# VXX2SCH.net
KiCad netlist of a schematic drawn in Altium Designer
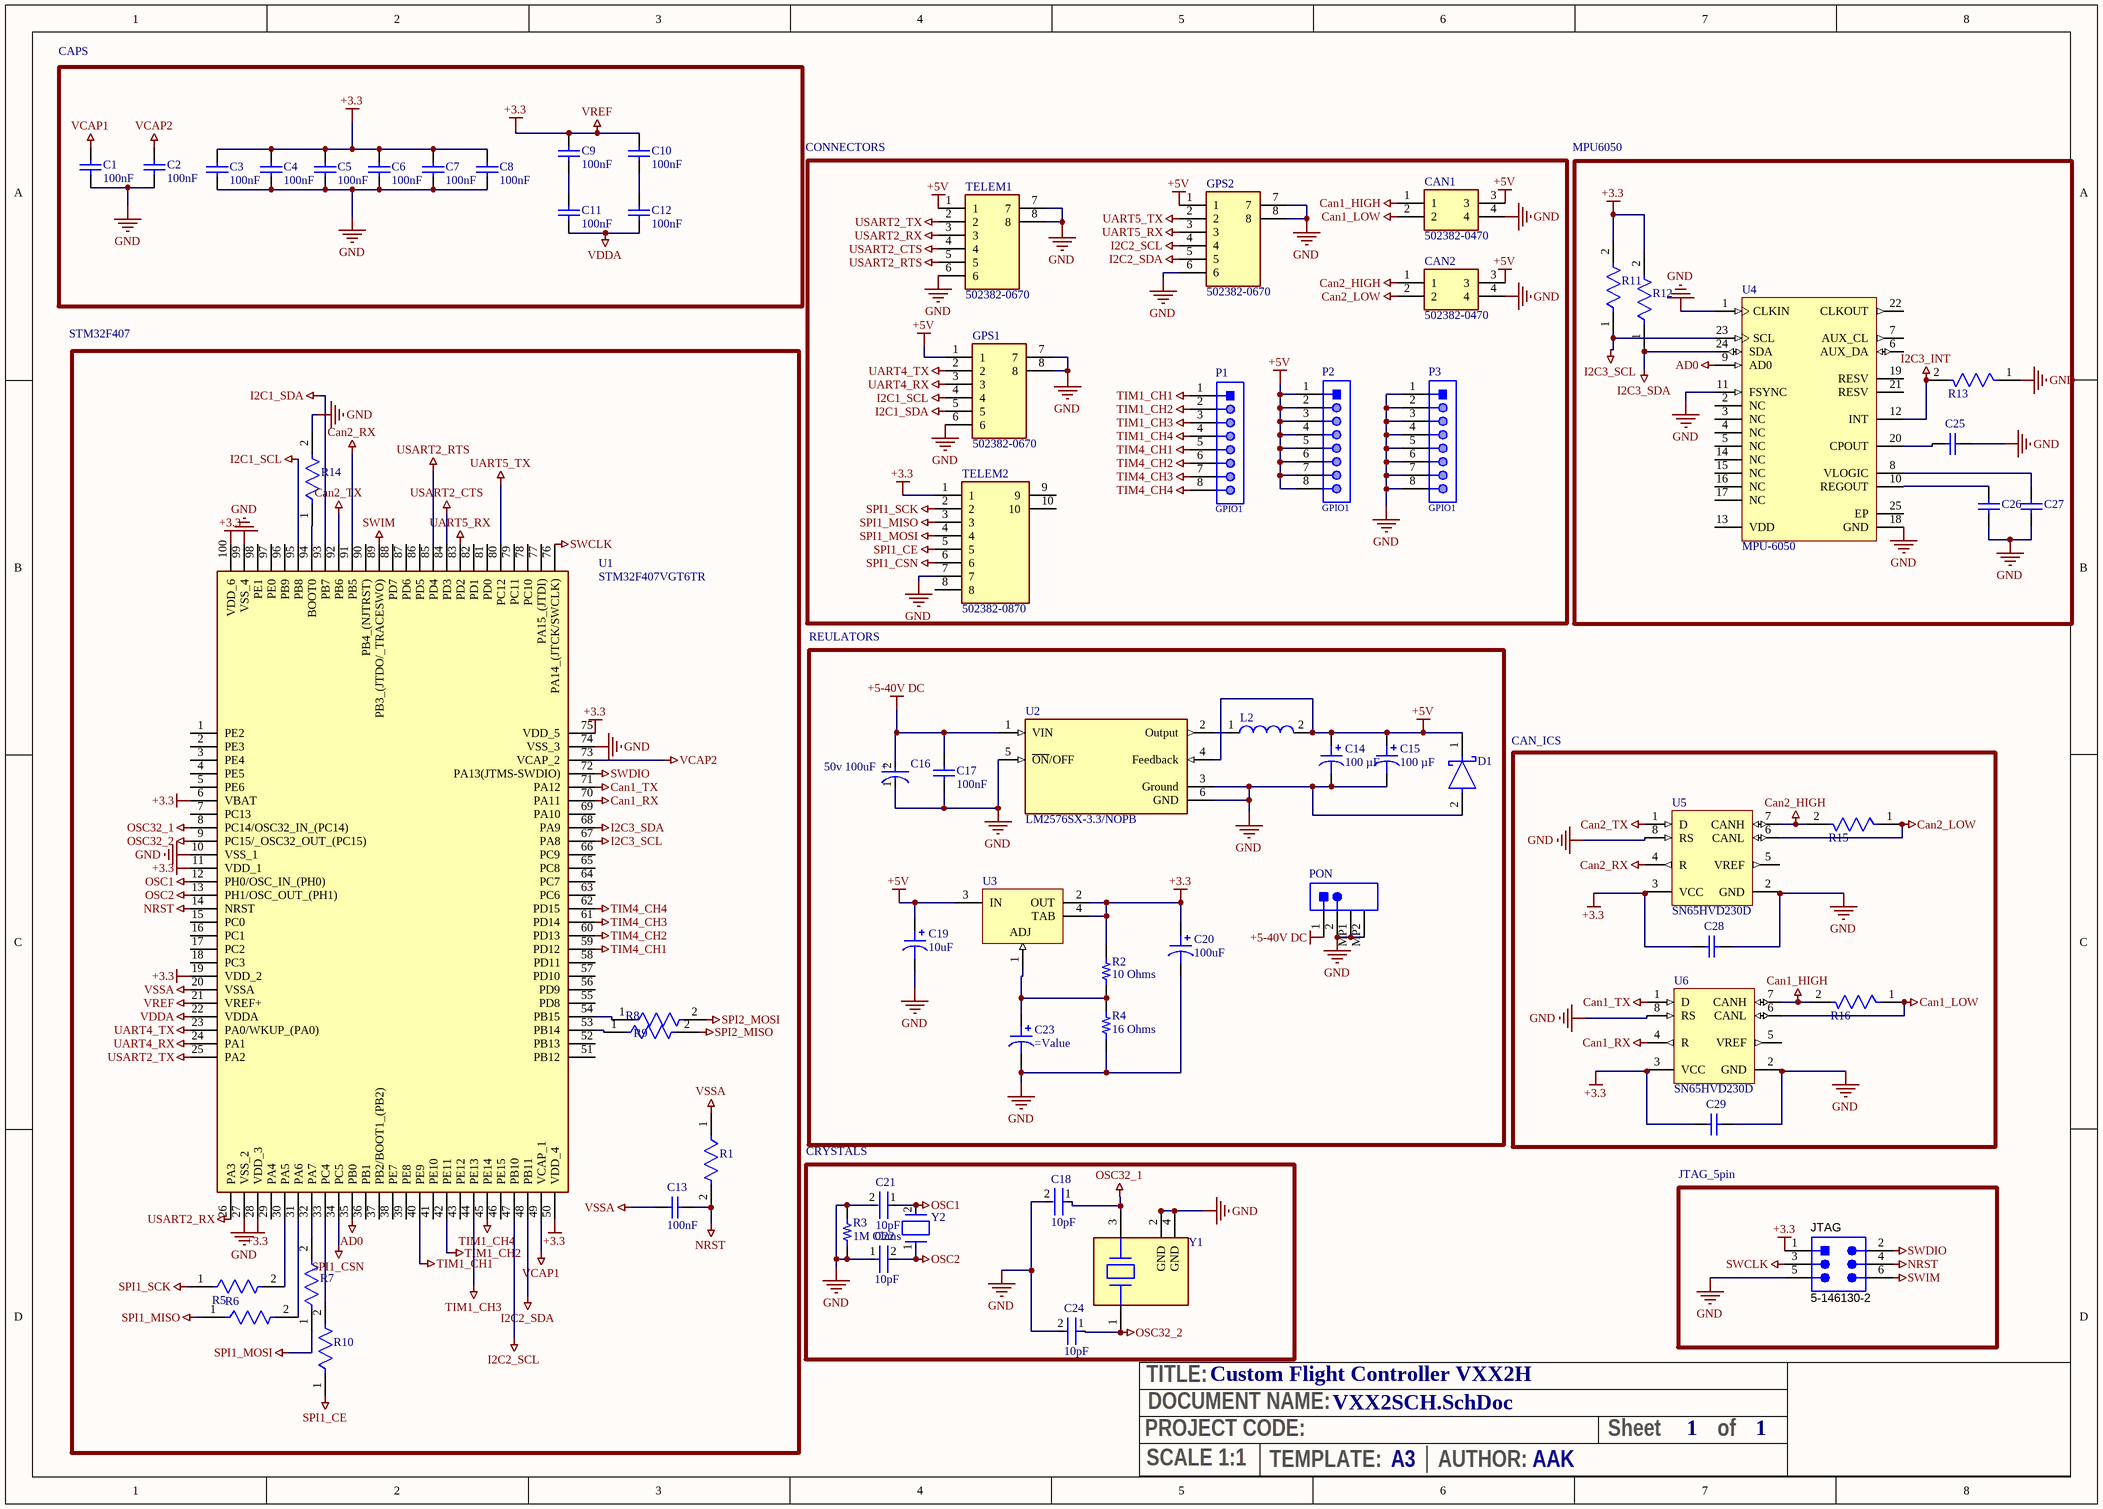
[diagram p0: VXX2SCH.SchDoc]

(export (version "E")
  (design (tool "Eeschema 10.0.6"))
  (components
    (comp (ref "C1")
      (value "100nF")
      (footprint "CAPC2013X135X45ML10T25")
      (description "Chip Capacitor, 0.1 uF, +/- 10%, 50 V, -55 to 125 degC, 0805 (2012 Metric), RoHS, Tape and Reel")
      (fields (field (name "VOLTAGE") "50V") (field (name "TOLERANCE") "10%"))
      (libsource (lib "Altium Content Vault") (part "CAP-NP-2"))
    )
    (comp (ref "C2")
      (value "100nF")
      (footprint "CAPC2013X135X45ML10T25")
      (description "Chip Capacitor, 0.1 uF, +/- 10%, 50 V, -55 to 125 degC, 0805 (2012 Metric), RoHS, Tape and Reel")
      (fields (field (name "VOLTAGE") "50V") (field (name "TOLERANCE") "10%"))
      (libsource (lib "Altium Content Vault") (part "CAP-NP-2"))
    )
    (comp (ref "C3")
      (value "100nF")
      (footprint "CAPC2013X135X45ML10T25")
      (description "Chip Capacitor, 0.1 uF, +/- 10%, 50 V, -55 to 125 degC, 0805 (2012 Metric), RoHS, Tape and Reel")
      (fields (field (name "VOLTAGE") "50V") (field (name "TOLERANCE") "10%"))
      (libsource (lib "Altium Content Vault") (part "CAP-NP-2"))
    )
    (comp (ref "C4")
      (value "100nF")
      (footprint "CAPC2013X135X45ML10T25")
      (description "Chip Capacitor, 0.1 uF, +/- 10%, 50 V, -55 to 125 degC, 0805 (2012 Metric), RoHS, Tape and Reel")
      (fields (field (name "VOLTAGE") "50V") (field (name "TOLERANCE") "10%"))
      (libsource (lib "Altium Content Vault") (part "CAP-NP-2"))
    )
    (comp (ref "C5")
      (value "100nF")
      (footprint "CAPC2013X135X45ML10T25")
      (description "Chip Capacitor, 0.1 uF, +/- 10%, 50 V, -55 to 125 degC, 0805 (2012 Metric), RoHS, Tape and Reel")
      (fields (field (name "VOLTAGE") "50V") (field (name "TOLERANCE") "10%"))
      (libsource (lib "Altium Content Vault") (part "CAP-NP-2"))
    )
    (comp (ref "C6")
      (value "100nF")
      (footprint "CAPC2013X135X45ML10T25")
      (description "Chip Capacitor, 0.1 uF, +/- 10%, 50 V, -55 to 125 degC, 0805 (2012 Metric), RoHS, Tape and Reel")
      (fields (field (name "VOLTAGE") "50V") (field (name "TOLERANCE") "10%"))
      (libsource (lib "Altium Content Vault") (part "CAP-NP-2"))
    )
    (comp (ref "C7")
      (value "100nF")
      (footprint "CAPC2013X135X45ML10T25")
      (description "Chip Capacitor, 0.1 uF, +/- 10%, 50 V, -55 to 125 degC, 0805 (2012 Metric), RoHS, Tape and Reel")
      (fields (field (name "VOLTAGE") "50V") (field (name "TOLERANCE") "10%"))
      (libsource (lib "Altium Content Vault") (part "CAP-NP-2"))
    )
    (comp (ref "C8")
      (value "100nF")
      (footprint "CAPC2013X135X45ML10T25")
      (description "Chip Capacitor, 0.1 uF, +/- 10%, 50 V, -55 to 125 degC, 0805 (2012 Metric), RoHS, Tape and Reel")
      (fields (field (name "VOLTAGE") "50V") (field (name "TOLERANCE") "10%"))
      (libsource (lib "Altium Content Vault") (part "CAP-NP-2"))
    )
    (comp (ref "C9")
      (value "100nF")
      (footprint "CAPC2013X135X45ML10T25")
      (description "Chip Capacitor, 0.1 uF, +/- 10%, 50 V, -55 to 125 degC, 0805 (2012 Metric), RoHS, Tape and Reel")
      (fields (field (name "VOLTAGE") "50V") (field (name "TOLERANCE") "10%"))
      (libsource (lib "Altium Content Vault") (part "CAP-NP-2"))
    )
    (comp (ref "C10")
      (value "100nF")
      (footprint "CAPC2013X135X45ML10T25")
      (description "Chip Capacitor, 0.1 uF, +/- 10%, 50 V, -55 to 125 degC, 0805 (2012 Metric), RoHS, Tape and Reel")
      (fields (field (name "VOLTAGE") "50V") (field (name "TOLERANCE") "10%"))
      (libsource (lib "Altium Content Vault") (part "CAP-NP-2"))
    )
    (comp (ref "C11")
      (value "100nF")
      (footprint "CAPC2013X135X45ML10T25")
      (description "Chip Capacitor, 0.1 uF, +/- 10%, 50 V, -55 to 125 degC, 0805 (2012 Metric), RoHS, Tape and Reel")
      (fields (field (name "VOLTAGE") "50V") (field (name "TOLERANCE") "10%"))
      (libsource (lib "Altium Content Vault") (part "CAP-NP-2"))
    )
    (comp (ref "C12")
      (value "100nF")
      (footprint "CAPC2013X135X45ML10T25")
      (description "Chip Capacitor, 0.1 uF, +/- 10%, 50 V, -55 to 125 degC, 0805 (2012 Metric), RoHS, Tape and Reel")
      (fields (field (name "VOLTAGE") "50V") (field (name "TOLERANCE") "10%"))
      (libsource (lib "Altium Content Vault") (part "CAP-NP-2"))
    )
    (comp (ref "C13")
      (value "100nF")
      (footprint "CAPC2013X135X45ML10T25")
      (description "Chip Capacitor, 0.1 uF, +/- 10%, 50 V, -55 to 125 degC, 0805 (2012 Metric), RoHS, Tape and Reel")
      (fields (field (name "VOLTAGE") "50V") (field (name "TOLERANCE") "10%"))
      (libsource (lib "Altium Content Vault") (part "CAP-NP-2"))
    )
    (comp (ref "C14")
      (value "100 µF")
      (footprint "CAP ALSMD 6.6MM H8.0MM")
      (description "CAP ALUM 100UF 20% 25V SMD")
      (fields (field (name "PART NUMBER") "UCD1E101MCL1GS") (field (name "MANUFACTURER") "Nichicon"))
      (libsource (lib "Celestial Altium Library - altium_library") (part "Polarised Capacitor"))
    )
    (comp (ref "C15")
      (value "100 µF")
      (footprint "CAP ALSMD 6.6MM H8.0MM")
      (description "CAP ALUM 100UF 20% 25V SMD")
      (fields (field (name "PART NUMBER") "UCD1E101MCL1GS") (field (name "MANUFACTURER") "Nichicon"))
      (libsource (lib "Celestial Altium Library - altium_library") (part "Polarised Capacitor"))
    )
    (comp (ref "C16")
      (value "50v 100uF")
      (footprint "FP-SC-MFG")
      (description "CAP ALUM 10UF 20% 35V SMD")
      (fields (field (name "TOLERANCE") "20%") (field (name "VOLTAGE") "35V"))
      (libsource (lib "Altium Content Vault") (part "203bc49f2ac43e59fd269a8c329ed05"))
    )
    (comp (ref "C17")
      (value "100nF")
      (footprint "CAPC2013X135X45ML10T25")
      (description "Chip Capacitor, 0.1 uF, +/- 10%, 50 V, -55 to 125 degC, 0805 (2012 Metric), RoHS, Tape and Reel")
      (fields (field (name "VOLTAGE") "50V") (field (name "TOLERANCE") "10%"))
      (libsource (lib "Altium Content Vault") (part "CAP-NP-2"))
    )
    (comp (ref "C18")
      (value "10pF")
      (footprint "FP-C0805C-DN-MFG")
      (description "Capacitor; Ceramic; Cap 10 pF; Tol 5%; Vol-Rtg 50 VDC; SMT; 0805; COG (NPO); Tape&Reel")
      (fields
        (field (name "OCTOPART") "https://octopart.com/c0805c100j5gactu-kemet-104357")
        (field (name "MANUFACTURER PART NUMBER") "C0805C100J5GACTU")
      )
      (libsource (lib "Altium Content Vault") (part "b4654b650e69147ec39a6b967a45e02"))
    )
    (comp (ref "C19")
      (value "10uF")
      (footprint "CAP ALSMD 4.3MM H5.4MM")
      (description "CAP ALUM 10UF 20% 16V SMD")
      (fields (field (name "PART NUMBER") "UWX1C100MCL1GB"))
      (libsource (lib "Celestial Altium Library - altium_library") (part "Polarised Capacitor"))
    )
    (comp (ref "C20")
      (value "100uF")
      (footprint "CAP ALSMD 4.3MM H5.4MM")
      (description "CAP ALUM 10UF 20% 16V SMD")
      (fields (field (name "PART NUMBER") "UWX1C100MCL1GB"))
      (libsource (lib "Celestial Altium Library - altium_library") (part "Polarised Capacitor"))
    )
    (comp (ref "C21")
      (value "10pF")
      (footprint "FP-C0805C-DN-MFG")
      (description "Capacitor; Ceramic; Cap 10 pF; Tol 5%; Vol-Rtg 50 VDC; SMT; 0805; COG (NPO); Tape&Reel")
      (fields
        (field (name "OCTOPART") "https://octopart.com/c0805c100j5gactu-kemet-104357")
        (field (name "MANUFACTURER PART NUMBER") "C0805C100J5GACTU")
      )
      (libsource (lib "Altium Content Vault") (part "b4654b650e69147ec39a6b967a45e02"))
    )
    (comp (ref "C22")
      (value "10pF")
      (footprint "FP-C0805C-DN-MFG")
      (description "Capacitor; Ceramic; Cap 10 pF; Tol 5%; Vol-Rtg 50 VDC; SMT; 0805; COG (NPO); Tape&Reel")
      (fields
        (field (name "OCTOPART") "https://octopart.com/c0805c100j5gactu-kemet-104357")
        (field (name "MANUFACTURER PART NUMBER") "C0805C100J5GACTU")
      )
      (libsource (lib "Altium Content Vault") (part "b4654b650e69147ec39a6b967a45e02"))
    )
    (comp (ref "C23")
      (value "~")
      (footprint "CAP ALSMD 4.3MM H5.4MM")
      (description "CAP ALUM 10UF 20% 16V SMD")
      (fields (field (name "PART NUMBER") "UWX1C100MCL1GB"))
      (libsource (lib "Celestial Altium Library - altium_library") (part "Polarised Capacitor"))
    )
    (comp (ref "C24")
      (value "10pF")
      (footprint "FP-C0805C-DN-MFG")
      (description "Capacitor; Ceramic; Cap 10 pF; Tol 5%; Vol-Rtg 50 VDC; SMT; 0805; COG (NPO); Tape&Reel")
      (fields
        (field (name "OCTOPART") "https://octopart.com/c0805c100j5gactu-kemet-104357")
        (field (name "MANUFACTURER PART NUMBER") "C0805C100J5GACTU")
      )
      (libsource (lib "Altium Content Vault") (part "b4654b650e69147ec39a6b967a45e02"))
    )
    (comp (ref "C25")
      (value "GRM188R71H222KA01D")
      (footprint "CAPC1608X90X35NL10T15")
      (description "Chip Capacitor, 2.2 nF, +/- 10%, 50 V, -55 to 125 degC, 0603 (1608 Metric), RoHS, Tape and Reel")
      (fields (field (name "MANUFACTURER") "Murata"))
      (libsource (lib "") (part "CAP-NP-2_1"))
    )
    (comp (ref "C26")
      (value "GRM188R71H222KA01D")
      (footprint "CAPC1608X90X35NL10T15")
      (description "Chip Capacitor, 2.2 nF, +/- 10%, 50 V, -55 to 125 degC, 0603 (1608 Metric), RoHS, Tape and Reel")
      (fields (field (name "MANUFACTURER") "Murata"))
      (libsource (lib "") (part "CAP-NP-2_1"))
    )
    (comp (ref "C27")
      (value "GRM188R71H222KA01D")
      (footprint "CAPC1608X90X35NL10T15")
      (description "Chip Capacitor, 2.2 nF, +/- 10%, 50 V, -55 to 125 degC, 0603 (1608 Metric), RoHS, Tape and Reel")
      (fields (field (name "MANUFACTURER") "Murata"))
      (libsource (lib "") (part "CAP-NP-2_1"))
    )
    (comp (ref "C28")
      (value "GRM188R71H222KA01D")
      (footprint "CAPC1608X90X35NL10T15")
      (description "Chip Capacitor, 2.2 nF, +/- 10%, 50 V, -55 to 125 degC, 0603 (1608 Metric), RoHS, Tape and Reel")
      (fields (field (name "MANUFACTURER") "Murata"))
      (libsource (lib "") (part "CAP-NP-2_1"))
    )
    (comp (ref "C29")
      (value "GRM188R71H222KA01D")
      (footprint "CAPC1608X90X35NL10T15")
      (description "Chip Capacitor, 2.2 nF, +/- 10%, 50 V, -55 to 125 degC, 0603 (1608 Metric), RoHS, Tape and Reel")
      (fields (field (name "MANUFACTURER") "Murata"))
      (libsource (lib "") (part "CAP-NP-2_1"))
    )
    (comp (ref "CAN1")
      (value "502382-0470")
      (footprint "SamacSys:502382-0470")
      (description "Connector")
      (fields (field (name "MOUSER PART NUMBER") "538-502382-0470"))
      (libsource (lib "*") (part "502382-0470"))
    )
    (comp (ref "CAN2")
      (value "502382-0470")
      (footprint "SamacSys:502382-0470")
      (description "Connector")
      (fields (field (name "MOUSER PART NUMBER") "538-502382-0470"))
      (libsource (lib "*") (part "502382-0470"))
    )
    (comp (ref "D1")
      (value "MBR0560-TP")
      (footprint "FP-SOD-123-IPC_C")
      (description "DIODE SCHOTTKY 60V 500MA SOD123")
      (libsource (lib "Altium Content Vault") (part "1d6ec82d83fb6aee721767c19dac4b9"))
    )
    (comp (ref "GPS1")
      (value "502382-0670")
      (footprint "SamacSys:5023820671")
      (description "Connector")
      (fields (field (name "MOUSER PART NUMBER") "538-502382-0670"))
      (libsource (lib "*") (part "502382-0670"))
    )
    (comp (ref "GPS2")
      (value "502382-0670")
      (footprint "SamacSys:5023820671")
      (description "Connector")
      (fields (field (name "MOUSER PART NUMBER") "538-502382-0670"))
      (libsource (lib "*") (part "502382-0670"))
    )
    (comp (ref "JTAG")
      (value "5-146130-2")
      (footprint "TECO-5-146130-2_V")
      (description "Male Header, Pitch 2.54 mm, 2 x 3 Position, Height 8.13 mm, -65 to 125 degC, RoHS, Tube")
      (libsource (lib "Altium Content Vault") (part "CN-2P-M-R6"))
    )
    (comp (ref "L2")
      (value "7447785147")
      (footprint "WE-PD-XS-PB")
      (description "SMD-Shielded Power Inductor WE-PD, L = 47.0 µH")
      (libsource (lib "Altium Content Vault") (part "PAS-IND-INDUCTOR-2"))
    )
    (comp (ref "P1")
      (value "GPIO1")
      (footprint "61300811121")
      (description "THT Vertical Pin Header WR-PHD, Pitch 2.54 mm, Single Row, 8 pins")
      (fields
        (field (name "MANUFACTURER") "Wurth Elektronik")
        (field (name "PART NUMBER") "61300811121")
        (field (name "PUBLISHER") "WurthElektronik")
      )
      (libsource (lib "Altium Content Vault") (part "WE-CN-1P-M-R8"))
    )
    (comp (ref "P2")
      (value "GPIO1")
      (footprint "61300811121")
      (description "THT Vertical Pin Header WR-PHD, Pitch 2.54 mm, Single Row, 8 pins")
      (fields
        (field (name "MANUFACTURER") "Wurth Elektronik")
        (field (name "PART NUMBER") "61300811121")
        (field (name "PUBLISHER") "WurthElektronik")
      )
      (libsource (lib "Altium Content Vault") (part "WE-CN-1P-M-R8"))
    )
    (comp (ref "P3")
      (value "GPIO1")
      (footprint "61300811121")
      (description "THT Vertical Pin Header WR-PHD, Pitch 2.54 mm, Single Row, 8 pins")
      (fields
        (field (name "MANUFACTURER") "Wurth Elektronik")
        (field (name "PART NUMBER") "61300811121")
        (field (name "PUBLISHER") "WurthElektronik")
      )
      (libsource (lib "Altium Content Vault") (part "WE-CN-1P-M-R8"))
    )
    (comp (ref "PON")
      (value "53398-0271")
      (footprint "MOLX-53398-0271_V")
      (description "Male Header, Pitch 1.25 mm, 1 x 2 Position, Height 4.7 mm, -40 to 85 degC, RoHS, Tape and Reel")
      (fields (field (name "MANUFACTURER") "Molex"))
      (libsource (lib "Altium Content Vault") (part "CN-1P-2M-R2"))
    )
    (comp (ref "R1")
      (value "RC0603FR-0710KL")
      (footprint "FP-RC0603-0_55-IPC_C")
      (description "RES 10K OHM 1% 1/10W 0603")
      (fields (field (name "TOLERANCE") "1%"))
      (libsource (lib "Altium Content Vault") (part "1029c3af85768c4190bb7ad29bc67b5"))
    )
    (comp (ref "R2")
      (value "10 Ohms")
      (footprint "RES 0603_1608")
      (description "RES 10K OHM 0.1% 1/16W 0603")
      (fields
        (field (name "PART NUMBER") "RNCS0603BKE10K0")
        (field (name "MANUFACTURER") "Stackpole Electronics Inc")
      )
      (libsource (lib "Celestial Altium Library - altium_library") (part "Resistor"))
    )
    (comp (ref "R3")
      (value "1M Ohms")
      (footprint "RES 0603_1608")
      (description "RES 10K OHM 0.1% 1/16W 0603")
      (fields
        (field (name "PART NUMBER") "RNCS0603BKE10K0")
        (field (name "MANUFACTURER") "Stackpole Electronics Inc")
      )
      (libsource (lib "Celestial Altium Library - altium_library") (part "Resistor"))
    )
    (comp (ref "R4")
      (value "16 Ohms")
      (footprint "RES 0603_1608")
      (description "RES 10K OHM 0.1% 1/16W 0603")
      (fields
        (field (name "PART NUMBER") "RNCS0603BKE10K0")
        (field (name "MANUFACTURER") "Stackpole Electronics Inc")
      )
      (libsource (lib "Celestial Altium Library - altium_library") (part "Resistor"))
    )
    (comp (ref "R5")
      (value "RC0603FR-07100L")
      (footprint "FP-RC0603-0_55-IPC_C")
      (description "RES 100 OHM 1% 1/10W 0603")
      (fields (field (name "TOLERANCE") "1%"))
      (libsource (lib "Altium Content Vault") (part "1029c3af85768c4190bb7ad29bc67b5"))
    )
    (comp (ref "R6")
      (value "RC0603FR-07100L")
      (footprint "FP-RC0603-0_55-IPC_C")
      (description "RES 100 OHM 1% 1/10W 0603")
      (fields (field (name "TOLERANCE") "1%"))
      (libsource (lib "Altium Content Vault") (part "1029c3af85768c4190bb7ad29bc67b5"))
    )
    (comp (ref "R7")
      (value "RC0603FR-07100L")
      (footprint "FP-RC0603-0_55-IPC_C")
      (description "RES 100 OHM 1% 1/10W 0603")
      (fields (field (name "TOLERANCE") "1%"))
      (libsource (lib "Altium Content Vault") (part "1029c3af85768c4190bb7ad29bc67b5"))
    )
    (comp (ref "R8")
      (value "RC0603FR-07100L")
      (footprint "FP-RC0603-0_55-IPC_C")
      (description "RES 100 OHM 1% 1/10W 0603")
      (fields (field (name "TOLERANCE") "1%"))
      (libsource (lib "Altium Content Vault") (part "1029c3af85768c4190bb7ad29bc67b5"))
    )
    (comp (ref "R9")
      (value "RC0603FR-07100L")
      (footprint "FP-RC0603-0_55-IPC_C")
      (description "RES 100 OHM 1% 1/10W 0603")
      (fields (field (name "TOLERANCE") "1%"))
      (libsource (lib "Altium Content Vault") (part "1029c3af85768c4190bb7ad29bc67b5"))
    )
    (comp (ref "R10")
      (value "RC0603FR-07100L")
      (footprint "FP-RC0603-0_55-IPC_C")
      (description "RES 100 OHM 1% 1/10W 0603")
      (fields (field (name "TOLERANCE") "1%"))
      (libsource (lib "Altium Content Vault") (part "1029c3af85768c4190bb7ad29bc67b5"))
    )
    (comp (ref "R11")
      (value "RC0603FR-07100L")
      (footprint "FP-RC0603-0_55-IPC_C")
      (description "RES 100 OHM 1% 1/10W 0603")
      (fields (field (name "TOLERANCE") "1%"))
      (libsource (lib "Altium Content Vault") (part "1029c3af85768c4190bb7ad29bc67b5"))
    )
    (comp (ref "R12")
      (value "RC0603FR-07100L")
      (footprint "FP-RC0603-0_55-IPC_C")
      (description "RES 100 OHM 1% 1/10W 0603")
      (fields (field (name "TOLERANCE") "1%"))
      (libsource (lib "Altium Content Vault") (part "1029c3af85768c4190bb7ad29bc67b5"))
    )
    (comp (ref "R13")
      (value "RC0603FR-07100L")
      (footprint "FP-RC0603-0_55-IPC_C")
      (description "RES 100 OHM 1% 1/10W 0603")
      (fields (field (name "TOLERANCE") "1%"))
      (libsource (lib "Altium Content Vault") (part "1029c3af85768c4190bb7ad29bc67b5"))
    )
    (comp (ref "R14")
      (value "RC0603FR-0710KL")
      (footprint "FP-RC0603-0_55-IPC_C")
      (description "RES 10K OHM 1% 1/10W 0603")
      (fields (field (name "TOLERANCE") "1%"))
      (libsource (lib "Altium Content Vault") (part "1029c3af85768c4190bb7ad29bc67b5"))
    )
    (comp (ref "R15")
      (value "RC0603FR-07100L")
      (footprint "FP-RC0603-0_55-IPC_C")
      (description "RES 120 OHM 1% 1/10W 0603")
      (fields (field (name "TOLERANCE") "1%"))
      (libsource (lib "Altium Content Vault") (part "1029c3af85768c4190bb7ad29bc67b5"))
    )
    (comp (ref "R16")
      (value "RC0603FR-07100L")
      (footprint "FP-RC0603-0_55-IPC_C")
      (description "RES 120 OHM 1% 1/10W 0603")
      (fields (field (name "TOLERANCE") "1%"))
      (libsource (lib "Altium Content Vault") (part "1029c3af85768c4190bb7ad29bc67b5"))
    )
    (comp (ref "TELEM1")
      (value "502382-0670")
      (footprint "SamacSys:5023820671")
      (description "Connector")
      (fields (field (name "MOUSER PART NUMBER") "538-502382-0670"))
      (libsource (lib "*") (part "502382-0670"))
    )
    (comp (ref "TELEM2")
      (value "502382-0870")
      (footprint "SamacSys:5023820870")
      (description "Connector")
      (fields (field (name "MOUSER PART NUMBER") "538-502382-0870"))
      (libsource (lib "*") (part "502382-0870"))
    )
    (comp (ref "U1")
      (value "STM32F407VGT6TR")
      (footprint "SamacSys:QFP50P1600X1600X160-100N")
      (description "Integrated Circuit")
      (fields (field (name "MOUSER PART NUMBER") "511-STM32F407VGT6TR"))
      (libsource (lib "*") (part "STM32F407VGT6TR"))
    )
    (comp (ref "U2")
      (value "LM2576SX-3.3/NOPB")
      (footprint "FP-KTT0005B-MFG")
      (description "IC REG BUCK 5V 3A TO263-5")
      (libsource (lib "Altium Content Vault") (part "f0883da41c58ceda5f27a37e32163a8"))
    )
    (comp (ref "U3")
      (value "LM1117MPX-ADJ/NOPB")
      (footprint "DCY0004A_N")
      (description "800mA Low-Dropout Linear Regulator, 4-pin SOT-223, Pb-Free")
      (fields (field (name "MANUFACTURER") "Texas Instruments"))
      (libsource (lib "Altium Content Vault") (part "PM-REG-LM1086ADJ-SOT4"))
    )
    (comp (ref "U4")
      (value "MPU-6050")
      (footprint "IS-QFN-24_V")
      (fields (field (name "MANUFACTURER") "InvenSense"))
      (libsource (lib "Altium Content Vault") (part "IS-MPU-6050-QFN-24"))
    )
    (comp (ref "U5")
      (value "SN65HVD230D")
      (footprint "D0008A_M")
      (description "CAN Bus Transceiver, 3.3 V, -40 to 85 degC, 8-Pin SOIC (D), Green (RoHS & no Sb/Br), Tube")
      (fields (field (name "GENERIC PART NUMBER") "SN65HVD230"))
      (libsource (lib "Altium Content Vault") (part "TI-SN65HVD230D-SOIC_D-8"))
    )
    (comp (ref "U6")
      (value "SN65HVD230D")
      (footprint "D0008A_M")
      (description "CAN Bus Transceiver, 3.3 V, -40 to 85 degC, 8-Pin SOIC (D), Green (RoHS & no Sb/Br), Tube")
      (fields (field (name "GENERIC PART NUMBER") "SN65HVD230"))
      (libsource (lib "Altium Content Vault") (part "TI-SN65HVD230D-SOIC_D-8"))
    )
    (comp (ref "Y1")
      (value "ABM3B-155-12.800MHZ-T")
      (footprint "FP-ABM3B-MFG")
      (description "Crystal 12.8MHz ±10ppm 15pF SMD-4 5mm x 3.2mm")
      (fields (field (name "TOLERANCE") "50ppm"))
      (libsource (lib "Altium Content Vault") (part "48e526d86b7f2615d98721063c72f49"))
    )
    (comp (ref "Y2")
      (value "ABM3-8.000MHZ-D2Y-T")
      (footprint "FP-ABM3-MFG")
      (description "Crystal 8MHz ±20ppm 18pF SMD-2 5mm x 3.2mm")
      (fields (field (name "TOLERANCE") "20ppm"))
      (libsource (lib "Altium Content Vault") (part "c23a69dc6c9e2f18f2079038eb95dd1"))
    )
  )
  (nets
    (net (code "1") (name "+3.3") (class "Default")
      (node (ref "C10") (pin "2") (pinfunction "2_2") (pintype "passive"))
      (node (ref "C20") (pin "1") (pinfunction "1_1") (pintype "passive"))
      (node (ref "C28") (pin "1") (pinfunction "1_1") (pintype "passive"))
      (node (ref "C29") (pin "1") (pinfunction "1_1") (pintype "passive"))
      (node (ref "C3") (pin "2") (pinfunction "2_2") (pintype "passive"))
      (node (ref "C4") (pin "2") (pinfunction "2_2") (pintype "passive"))
      (node (ref "C5") (pin "2") (pinfunction "2_2") (pintype "passive"))
      (node (ref "C6") (pin "2") (pinfunction "2_2") (pintype "passive"))
      (node (ref "C7") (pin "2") (pinfunction "2_2") (pintype "passive"))
      (node (ref "C8") (pin "2") (pinfunction "2_2") (pintype "passive"))
      (node (ref "C9") (pin "2") (pinfunction "2_2") (pintype "passive"))
      (node (ref "JTAG") (pin "1") (pinfunction "1_1") (pintype "passive"))
      (node (ref "R11") (pin "2") (pinfunction "2_2") (pintype "passive"))
      (node (ref "R12") (pin "2") (pinfunction "2_2") (pintype "passive"))
      (node (ref "R2") (pin "2") (pinfunction "2_2") (pintype "passive"))
      (node (ref "TELEM2") (pin "1") (pinfunction "1_1") (pintype "passive"))
      (node (ref "U1") (pin "100") (pinfunction "VDD_6_100") (pintype "passive"))
      (node (ref "U1") (pin "11") (pinfunction "VDD_1_11") (pintype "passive"))
      (node (ref "U1") (pin "19") (pinfunction "VDD_2_19") (pintype "passive"))
      (node (ref "U1") (pin "21") (pinfunction "VREF+_21") (pintype "passive"))
      (node (ref "U1") (pin "28") (pinfunction "VDD_3_28") (pintype "passive"))
      (node (ref "U1") (pin "50") (pinfunction "VDD_4_50") (pintype "passive"))
      (node (ref "U1") (pin "6") (pinfunction "VBAT_6") (pintype "passive"))
      (node (ref "U1") (pin "75") (pinfunction "VDD_5_75") (pintype "passive"))
      (node (ref "U3") (pin "2") (pinfunction "OUT_2") (pintype "power_in"))
      (node (ref "U3") (pin "4") (pinfunction "TAB_4") (pintype "power_in"))
      (node (ref "U5") (pin "3") (pinfunction "VCC_3") (pintype "power_in"))
      (node (ref "U6") (pin "3") (pinfunction "VCC_3") (pintype "power_in"))
    )
    (net (code "2") (name "+5-40V DC") (class "Default")
      (node (ref "C16") (pin "2") (pinfunction "A_2") (pintype "passive"))
      (node (ref "C17") (pin "2") (pinfunction "2_2") (pintype "passive"))
      (node (ref "PON") (pin "1") (pinfunction "1_1") (pintype "passive"))
      (node (ref "U2") (pin "1") (pinfunction "VIN_1") (pintype "input"))
    )
    (net (code "3") (name "+5V") (class "Default")
      (node (ref "C14") (pin "1") (pinfunction "1_1") (pintype "passive"))
      (node (ref "C15") (pin "1") (pinfunction "1_1") (pintype "passive"))
      (node (ref "C19") (pin "1") (pinfunction "1_1") (pintype "passive"))
      (node (ref "CAN1") (pin "3") (pinfunction "3_3") (pintype "passive"))
      (node (ref "CAN2") (pin "3") (pinfunction "3_3") (pintype "passive"))
      (node (ref "D1") (pin "1") (pinfunction "C_1") (pintype "passive"))
      (node (ref "GPS1") (pin "1") (pinfunction "1_1") (pintype "passive"))
      (node (ref "GPS2") (pin "1") (pinfunction "1_1") (pintype "passive"))
      (node (ref "L2") (pin "2") (pinfunction "2_2") (pintype "passive"))
      (node (ref "P2") (pin "1") (pinfunction "1_1") (pintype "passive"))
      (node (ref "P2") (pin "2") (pinfunction "2_2") (pintype "passive"))
      (node (ref "P2") (pin "3") (pinfunction "3_3") (pintype "passive"))
      (node (ref "P2") (pin "4") (pinfunction "4_4") (pintype "passive"))
      (node (ref "P2") (pin "5") (pinfunction "5_5") (pintype "passive"))
      (node (ref "P2") (pin "6") (pinfunction "6_6") (pintype "passive"))
      (node (ref "P2") (pin "7") (pinfunction "7_7") (pintype "passive"))
      (node (ref "P2") (pin "8") (pinfunction "8_8") (pintype "passive"))
      (node (ref "TELEM1") (pin "1") (pinfunction "1_1") (pintype "passive"))
      (node (ref "U2") (pin "4") (pinfunction "Feedback_4") (pintype "input"))
      (node (ref "U3") (pin "3") (pinfunction "IN_3") (pintype "power_in"))
    )
    (net (code "4") (name "AD0") (class "Default")
      (node (ref "U1") (pin "35") (pinfunction "PB0_35") (pintype "passive"))
      (node (ref "U4") (pin "9") (pinfunction "AD0_9") (pintype "input"))
    )
    (net (code "5") (name "Can1_HIGH") (class "Default")
      (node (ref "CAN1") (pin "1") (pinfunction "1_1") (pintype "passive"))
      (node (ref "R16") (pin "2") (pinfunction "2_2") (pintype "passive"))
      (node (ref "U6") (pin "7") (pinfunction "CANH_7") (pintype "bidirectional"))
    )
    (net (code "6") (name "Can1_LOW") (class "Default")
      (node (ref "CAN1") (pin "2") (pinfunction "2_2") (pintype "passive"))
      (node (ref "R16") (pin "1") (pinfunction "1_1") (pintype "passive"))
      (node (ref "U6") (pin "6") (pinfunction "CANL_6") (pintype "bidirectional"))
    )
    (net (code "7") (name "Can1_RX") (class "Default")
      (node (ref "U1") (pin "70") (pinfunction "PA11_70") (pintype "passive"))
      (node (ref "U6") (pin "4") (pinfunction "R_4") (pintype "output"))
    )
    (net (code "8") (name "Can1_TX") (class "Default")
      (node (ref "U1") (pin "71") (pinfunction "PA12_71") (pintype "passive"))
      (node (ref "U6") (pin "1") (pinfunction "D_1") (pintype "input"))
    )
    (net (code "9") (name "Can2_HIGH") (class "Default")
      (node (ref "CAN2") (pin "1") (pinfunction "1_1") (pintype "passive"))
      (node (ref "R15") (pin "2") (pinfunction "2_2") (pintype "passive"))
      (node (ref "U5") (pin "7") (pinfunction "CANH_7") (pintype "bidirectional"))
    )
    (net (code "10") (name "Can2_LOW") (class "Default")
      (node (ref "CAN2") (pin "2") (pinfunction "2_2") (pintype "passive"))
      (node (ref "R15") (pin "1") (pinfunction "1_1") (pintype "passive"))
      (node (ref "U5") (pin "6") (pinfunction "CANL_6") (pintype "bidirectional"))
    )
    (net (code "11") (name "Can2_RX") (class "Default")
      (node (ref "U1") (pin "91") (pinfunction "PB5_91") (pintype "passive"))
      (node (ref "U5") (pin "4") (pinfunction "R_4") (pintype "output"))
    )
    (net (code "12") (name "Can2_TX") (class "Default")
      (node (ref "U1") (pin "92") (pinfunction "PB6_92") (pintype "passive"))
      (node (ref "U5") (pin "1") (pinfunction "D_1") (pintype "input"))
    )
    (net (code "13") (name "GND") (class "Default")
      (node (ref "C1") (pin "1") (pinfunction "1_1") (pintype "passive"))
      (node (ref "C14") (pin "2") (pinfunction "2_2") (pintype "passive"))
      (node (ref "C15") (pin "2") (pinfunction "2_2") (pintype "passive"))
      (node (ref "C16") (pin "1") (pinfunction "C_1") (pintype "passive"))
      (node (ref "C17") (pin "1") (pinfunction "1_1") (pintype "passive"))
      (node (ref "C18") (pin "2") (pinfunction "2_2") (pintype "passive"))
      (node (ref "C19") (pin "2") (pinfunction "2_2") (pintype "passive"))
      (node (ref "C2") (pin "1") (pinfunction "1_1") (pintype "passive"))
      (node (ref "C20") (pin "2") (pinfunction "2_2") (pintype "passive"))
      (node (ref "C21") (pin "2") (pinfunction "2_2") (pintype "passive"))
      (node (ref "C22") (pin "1") (pinfunction "1_1") (pintype "passive"))
      (node (ref "C23") (pin "2") (pinfunction "2_2") (pintype "passive"))
      (node (ref "C24") (pin "2") (pinfunction "2_2") (pintype "passive"))
      (node (ref "C25") (pin "2") (pinfunction "2_2") (pintype "passive"))
      (node (ref "C26") (pin "2") (pinfunction "2_2") (pintype "passive"))
      (node (ref "C27") (pin "2") (pinfunction "2_2") (pintype "passive"))
      (node (ref "C28") (pin "2") (pinfunction "2_2") (pintype "passive"))
      (node (ref "C29") (pin "2") (pinfunction "2_2") (pintype "passive"))
      (node (ref "C3") (pin "1") (pinfunction "1_1") (pintype "passive"))
      (node (ref "C4") (pin "1") (pinfunction "1_1") (pintype "passive"))
      (node (ref "C5") (pin "1") (pinfunction "1_1") (pintype "passive"))
      (node (ref "C6") (pin "1") (pinfunction "1_1") (pintype "passive"))
      (node (ref "C7") (pin "1") (pinfunction "1_1") (pintype "passive"))
      (node (ref "C8") (pin "1") (pinfunction "1_1") (pintype "passive"))
      (node (ref "CAN1") (pin "4") (pinfunction "4_4") (pintype "passive"))
      (node (ref "CAN2") (pin "4") (pinfunction "4_4") (pintype "passive"))
      (node (ref "D1") (pin "2") (pinfunction "A_2") (pintype "passive"))
      (node (ref "GPS1") (pin "6") (pinfunction "6_6") (pintype "passive"))
      (node (ref "GPS1") (pin "7") (pinfunction "7_7") (pintype "passive"))
      (node (ref "GPS1") (pin "8") (pinfunction "8_8") (pintype "passive"))
      (node (ref "GPS2") (pin "6") (pinfunction "6_6") (pintype "passive"))
      (node (ref "GPS2") (pin "7") (pinfunction "7_7") (pintype "passive"))
      (node (ref "GPS2") (pin "8") (pinfunction "8_8") (pintype "passive"))
      (node (ref "JTAG") (pin "5") (pinfunction "5_5") (pintype "passive"))
      (node (ref "P3") (pin "1") (pinfunction "1_1") (pintype "passive"))
      (node (ref "P3") (pin "2") (pinfunction "2_2") (pintype "passive"))
      (node (ref "P3") (pin "3") (pinfunction "3_3") (pintype "passive"))
      (node (ref "P3") (pin "4") (pinfunction "4_4") (pintype "passive"))
      (node (ref "P3") (pin "5") (pinfunction "5_5") (pintype "passive"))
      (node (ref "P3") (pin "6") (pinfunction "6_6") (pintype "passive"))
      (node (ref "P3") (pin "7") (pinfunction "7_7") (pintype "passive"))
      (node (ref "P3") (pin "8") (pinfunction "8_8") (pintype "passive"))
      (node (ref "PON") (pin "2") (pinfunction "2_2") (pintype "passive"))
      (node (ref "PON") (pin "MP1") (pinfunction "MP1_MP1") (pintype "passive"))
      (node (ref "PON") (pin "MP2") (pinfunction "MP2_MP2") (pintype "passive"))
      (node (ref "R13") (pin "1") (pinfunction "1_1") (pintype "passive"))
      (node (ref "R14") (pin "2") (pinfunction "2_2") (pintype "passive"))
      (node (ref "R3") (pin "1") (pinfunction "1_1") (pintype "passive"))
      (node (ref "R3") (pin "2") (pinfunction "2_2") (pintype "passive"))
      (node (ref "R4") (pin "1") (pinfunction "1_1") (pintype "passive"))
      (node (ref "TELEM1") (pin "6") (pinfunction "6_6") (pintype "passive"))
      (node (ref "TELEM1") (pin "7") (pinfunction "7_7") (pintype "passive"))
      (node (ref "TELEM1") (pin "8") (pinfunction "8_8") (pintype "passive"))
      (node (ref "TELEM2") (pin "7") (pinfunction "7_7") (pintype "passive"))
      (node (ref "U1") (pin "10") (pinfunction "VSS_1_10") (pintype "passive"))
      (node (ref "U1") (pin "27") (pinfunction "VSS_2_27") (pintype "passive"))
      (node (ref "U1") (pin "74") (pinfunction "VSS_3_74") (pintype "passive"))
      (node (ref "U1") (pin "99") (pinfunction "VSS_4_99") (pintype "passive"))
      (node (ref "U2") (pin "3") (pinfunction "Ground_3") (pintype "power_in"))
      (node (ref "U2") (pin "5") (pinfunction "~{ON}/OFF_5") (pintype "input"))
      (node (ref "U2") (pin "6") (pinfunction "GND_6") (pintype "power_in"))
      (node (ref "U4") (pin "1") (pinfunction "CLKIN_1") (pintype "input"))
      (node (ref "U4") (pin "11") (pinfunction "FSYNC_11") (pintype "input"))
      (node (ref "U4") (pin "18") (pinfunction "GND_18") (pintype "power_in"))
      (node (ref "U5") (pin "2") (pinfunction "GND_2") (pintype "power_in"))
      (node (ref "U5") (pin "8") (pinfunction "RS_8") (pintype "input"))
      (node (ref "U6") (pin "2") (pinfunction "GND_2") (pintype "power_in"))
      (node (ref "U6") (pin "8") (pinfunction "RS_8") (pintype "input"))
      (node (ref "Y1") (pin "2") (pinfunction "GND_2") (pintype "power_in"))
      (node (ref "Y1") (pin "4") (pinfunction "GND_4") (pintype "power_in"))
    )
    (net (code "14") (name "I2C1_SCL") (class "Default")
      (node (ref "GPS1") (pin "4") (pinfunction "4_4") (pintype "passive"))
      (node (ref "U1") (pin "95") (pinfunction "PB8_95") (pintype "passive"))
    )
    (net (code "15") (name "I2C1_SDA") (class "Default")
      (node (ref "GPS1") (pin "5") (pinfunction "5_5") (pintype "passive"))
      (node (ref "U1") (pin "93") (pinfunction "PB7_93") (pintype "passive"))
    )
    (net (code "16") (name "I2C2_SCL") (class "Default")
      (node (ref "GPS2") (pin "4") (pinfunction "4_4") (pintype "passive"))
      (node (ref "U1") (pin "47") (pinfunction "PB10_47") (pintype "passive"))
    )
    (net (code "17") (name "I2C2_SDA") (class "Default")
      (node (ref "GPS2") (pin "5") (pinfunction "5_5") (pintype "passive"))
      (node (ref "U1") (pin "48") (pinfunction "PB11_48") (pintype "passive"))
    )
    (net (code "18") (name "I2C3_INT") (class "Default")
      (node (ref "R13") (pin "2") (pinfunction "2_2") (pintype "passive"))
      (node (ref "U4") (pin "12") (pinfunction "INT_12") (pintype "open_collector"))
    )
    (net (code "19") (name "I2C3_SCL") (class "Default")
      (node (ref "R11") (pin "1") (pinfunction "1_1") (pintype "passive"))
      (node (ref "U1") (pin "67") (pinfunction "PA8_67") (pintype "passive"))
      (node (ref "U4") (pin "23") (pinfunction "SCL_23") (pintype "input"))
    )
    (net (code "20") (name "I2C3_SDA") (class "Default")
      (node (ref "R12") (pin "1") (pinfunction "1_1") (pintype "passive"))
      (node (ref "U1") (pin "68") (pinfunction "PA9_68") (pintype "passive"))
      (node (ref "U4") (pin "24") (pinfunction "SDA_24") (pintype "bidirectional"))
    )
    (net (code "21") (name "NRST") (class "Default")
      (node (ref "C13") (pin "2") (pinfunction "2_2") (pintype "passive"))
      (node (ref "JTAG") (pin "4") (pinfunction "4_4") (pintype "passive"))
      (node (ref "R1") (pin "2") (pinfunction "2_2") (pintype "passive"))
      (node (ref "U1") (pin "14") (pinfunction "NRST_14") (pintype "passive"))
    )
    (net (code "22") (name "Net-(C10-Pad1)") (class "Default")
      (node (ref "C10") (pin "1") (pinfunction "1_1") (pintype "passive"))
      (node (ref "C12") (pin "2") (pinfunction "2_2") (pintype "passive"))
    )
    (net (code "23") (name "Net-(C11-Pad2)") (class "Default")
      (node (ref "C11") (pin "2") (pinfunction "2_2") (pintype "passive"))
      (node (ref "C9") (pin "1") (pinfunction "1_1") (pintype "passive"))
    )
    (net (code "24") (name "Net-(U1-BOOT0)") (class "Default")
      (node (ref "R14") (pin "1") (pinfunction "1_1") (pintype "passive"))
      (node (ref "U1") (pin "94") (pinfunction "BOOT0_94") (pintype "passive"))
    )
    (net (code "25") (name "Net-(U1-PA5)") (class "Default")
      (node (ref "R5") (pin "2") (pinfunction "2_2") (pintype "passive"))
      (node (ref "U1") (pin "30") (pinfunction "PA5_30") (pintype "passive"))
    )
    (net (code "26") (name "Net-(U1-PA6)") (class "Default")
      (node (ref "R6") (pin "2") (pinfunction "2_2") (pintype "passive"))
      (node (ref "U1") (pin "31") (pinfunction "PA6_31") (pintype "passive"))
    )
    (net (code "27") (name "Net-(U1-PA7)") (class "Default")
      (node (ref "R7") (pin "2") (pinfunction "2_2") (pintype "passive"))
      (node (ref "U1") (pin "32") (pinfunction "PA7_32") (pintype "passive"))
    )
    (net (code "28") (name "Net-(U1-PB14)") (class "Default")
      (node (ref "R8") (pin "1") (pinfunction "1_1") (pintype "passive"))
      (node (ref "U1") (pin "53") (pinfunction "PB14_53") (pintype "passive"))
    )
    (net (code "29") (name "Net-(U1-PB15)") (class "Default")
      (node (ref "R9") (pin "1") (pinfunction "1_1") (pintype "passive"))
      (node (ref "U1") (pin "54") (pinfunction "PB15_54") (pintype "passive"))
    )
    (net (code "30") (name "Net-(U1-PC4)") (class "Default")
      (node (ref "R10") (pin "2") (pinfunction "2_2") (pintype "passive"))
      (node (ref "U1") (pin "33") (pinfunction "PC4_33") (pintype "passive"))
    )
    (net (code "31") (name "Net-(U2-Output)") (class "Default")
      (node (ref "L2") (pin "1") (pinfunction "1_1") (pintype "passive"))
      (node (ref "U2") (pin "2") (pinfunction "Output_2") (pintype "output"))
    )
    (net (code "32") (name "Net-(U3-ADJ)") (class "Default")
      (node (ref "C23") (pin "1") (pinfunction "1_1") (pintype "passive"))
      (node (ref "R2") (pin "1") (pinfunction "1_1") (pintype "passive"))
      (node (ref "R4") (pin "2") (pinfunction "2_2") (pintype "passive"))
      (node (ref "U3") (pin "1") (pinfunction "ADJ_1") (pintype "input"))
    )
    (net (code "33") (name "Net-(U4-CPOUT)") (class "Default")
      (node (ref "C25") (pin "1") (pinfunction "1_1") (pintype "passive"))
      (node (ref "U4") (pin "20") (pinfunction "CPOUT_20") (pintype "passive"))
    )
    (net (code "34") (name "Net-(U4-REGOUT)") (class "Default")
      (node (ref "C26") (pin "1") (pinfunction "1_1") (pintype "passive"))
      (node (ref "U4") (pin "10") (pinfunction "REGOUT_10") (pintype "passive"))
    )
    (net (code "35") (name "Net-(U4-VLOGIC)") (class "Default")
      (node (ref "C27") (pin "1") (pinfunction "1_1") (pintype "passive"))
      (node (ref "U4") (pin "8") (pinfunction "VLOGIC_8") (pintype "power_in"))
    )
    (net (code "36") (name "OSC1") (class "Default")
      (node (ref "C21") (pin "1") (pinfunction "1_1") (pintype "passive"))
      (node (ref "U1") (pin "12") (pinfunction "PH0/OSC_IN_(PH0)_12") (pintype "passive"))
      (node (ref "Y2") (pin "2") (pinfunction "2_2") (pintype "passive"))
    )
    (net (code "37") (name "OSC2") (class "Default")
      (node (ref "C22") (pin "2") (pinfunction "2_2") (pintype "passive"))
      (node (ref "U1") (pin "13") (pinfunction "PH1/OSC_OUT_(PH1)_13") (pintype "passive"))
      (node (ref "Y2") (pin "1") (pinfunction "1_1") (pintype "passive"))
    )
    (net (code "38") (name "OSC32_1") (class "Default")
      (node (ref "C18") (pin "1") (pinfunction "1_1") (pintype "passive"))
      (node (ref "U1") (pin "8") (pinfunction "PC14/OSC32_IN_(PC14)_8") (pintype "passive"))
      (node (ref "Y1") (pin "3") (pinfunction "3_3") (pintype "passive"))
    )
    (net (code "39") (name "OSC32_2") (class "Default")
      (node (ref "C24") (pin "1") (pinfunction "1_1") (pintype "passive"))
      (node (ref "U1") (pin "9") (pinfunction "PC15/_OSC32_OUT_(PC15)_9") (pintype "passive"))
      (node (ref "Y1") (pin "1") (pinfunction "1_1") (pintype "passive"))
    )
    (net (code "40") (name "SPI1_CE") (class "Default")
      (node (ref "R10") (pin "1") (pinfunction "1_1") (pintype "passive"))
      (node (ref "TELEM2") (pin "5") (pinfunction "5_5") (pintype "passive"))
    )
    (net (code "41") (name "SPI1_CSN") (class "Default")
      (node (ref "TELEM2") (pin "6") (pinfunction "6_6") (pintype "passive"))
      (node (ref "U1") (pin "34") (pinfunction "PC5_34") (pintype "passive"))
    )
    (net (code "42") (name "SPI1_MISO") (class "Default")
      (node (ref "R6") (pin "1") (pinfunction "1_1") (pintype "passive"))
      (node (ref "TELEM2") (pin "3") (pinfunction "3_3") (pintype "passive"))
    )
    (net (code "43") (name "SPI1_MOSI") (class "Default")
      (node (ref "R7") (pin "1") (pinfunction "1_1") (pintype "passive"))
      (node (ref "TELEM2") (pin "4") (pinfunction "4_4") (pintype "passive"))
    )
    (net (code "44") (name "SPI1_SCK") (class "Default")
      (node (ref "R5") (pin "1") (pinfunction "1_1") (pintype "passive"))
      (node (ref "TELEM2") (pin "2") (pinfunction "2_2") (pintype "passive"))
    )
    (net (code "45") (name "SPI2_MISO") (class "Default")
      (node (ref "R8") (pin "2") (pinfunction "2_2") (pintype "passive"))
    )
    (net (code "46") (name "SPI2_MOSI") (class "Default")
      (node (ref "R9") (pin "2") (pinfunction "2_2") (pintype "passive"))
    )
    (net (code "47") (name "SWCLK") (class "Default")
      (node (ref "JTAG") (pin "3") (pinfunction "3_3") (pintype "passive"))
      (node (ref "U1") (pin "76") (pinfunction "PA14_(JTCK/SWCLK)_76") (pintype "passive"))
    )
    (net (code "48") (name "SWDIO") (class "Default")
      (node (ref "JTAG") (pin "2") (pinfunction "2_2") (pintype "passive"))
      (node (ref "U1") (pin "72") (pinfunction "PA13(JTMS-SWDIO)_72") (pintype "passive"))
    )
    (net (code "49") (name "SWIM") (class "Default")
      (node (ref "JTAG") (pin "6") (pinfunction "6_6") (pintype "passive"))
      (node (ref "U1") (pin "89") (pinfunction "PB3_(JTDO/_TRACESWO)_89") (pintype "passive"))
    )
    (net (code "50") (name "TIM1_CH1") (class "Default")
      (node (ref "P1") (pin "1") (pinfunction "1_1") (pintype "passive"))
      (node (ref "U1") (pin "40") (pinfunction "PE9_40") (pintype "passive"))
    )
    (net (code "51") (name "TIM1_CH2") (class "Default")
      (node (ref "P1") (pin "2") (pinfunction "2_2") (pintype "passive"))
      (node (ref "U1") (pin "42") (pinfunction "PE11_42") (pintype "passive"))
    )
    (net (code "52") (name "TIM1_CH3") (class "Default")
      (node (ref "P1") (pin "3") (pinfunction "3_3") (pintype "passive"))
      (node (ref "U1") (pin "44") (pinfunction "PE13_44") (pintype "passive"))
    )
    (net (code "53") (name "TIM1_CH4") (class "Default")
      (node (ref "P1") (pin "4") (pinfunction "4_4") (pintype "passive"))
      (node (ref "U1") (pin "45") (pinfunction "PE14_45") (pintype "passive"))
    )
    (net (code "54") (name "TIM4_CH1") (class "Default")
      (node (ref "P1") (pin "5") (pinfunction "5_5") (pintype "passive"))
      (node (ref "U1") (pin "59") (pinfunction "PD12_59") (pintype "passive"))
    )
    (net (code "55") (name "TIM4_CH2") (class "Default")
      (node (ref "P1") (pin "6") (pinfunction "6_6") (pintype "passive"))
      (node (ref "U1") (pin "60") (pinfunction "PD13_60") (pintype "passive"))
    )
    (net (code "56") (name "TIM4_CH3") (class "Default")
      (node (ref "P1") (pin "7") (pinfunction "7_7") (pintype "passive"))
      (node (ref "U1") (pin "61") (pinfunction "PD14_61") (pintype "passive"))
    )
    (net (code "57") (name "TIM4_CH4") (class "Default")
      (node (ref "P1") (pin "8") (pinfunction "8_8") (pintype "passive"))
      (node (ref "U1") (pin "62") (pinfunction "PD15_62") (pintype "passive"))
    )
    (net (code "58") (name "UART4_RX") (class "Default")
      (node (ref "GPS1") (pin "3") (pinfunction "3_3") (pintype "passive"))
      (node (ref "U1") (pin "24") (pinfunction "PA1_24") (pintype "passive"))
    )
    (net (code "59") (name "UART4_TX") (class "Default")
      (node (ref "GPS1") (pin "2") (pinfunction "2_2") (pintype "passive"))
      (node (ref "U1") (pin "23") (pinfunction "PA0/WKUP_(PA0)_23") (pintype "passive"))
    )
    (net (code "60") (name "UART5_RX") (class "Default")
      (node (ref "GPS2") (pin "3") (pinfunction "3_3") (pintype "passive"))
      (node (ref "U1") (pin "83") (pinfunction "PD2_83") (pintype "passive"))
    )
    (net (code "61") (name "UART5_TX") (class "Default")
      (node (ref "GPS2") (pin "2") (pinfunction "2_2") (pintype "passive"))
      (node (ref "U1") (pin "80") (pinfunction "PC12_80") (pintype "passive"))
    )
    (net (code "62") (name "USART2_CTS") (class "Default")
      (node (ref "TELEM1") (pin "4") (pinfunction "4_4") (pintype "passive"))
      (node (ref "U1") (pin "84") (pinfunction "PD3_84") (pintype "passive"))
    )
    (net (code "63") (name "USART2_RTS") (class "Default")
      (node (ref "TELEM1") (pin "5") (pinfunction "5_5") (pintype "passive"))
      (node (ref "U1") (pin "85") (pinfunction "PD4_85") (pintype "passive"))
    )
    (net (code "64") (name "USART2_RX") (class "Default")
      (node (ref "TELEM1") (pin "3") (pinfunction "3_3") (pintype "passive"))
      (node (ref "U1") (pin "26") (pinfunction "PA3_26") (pintype "passive"))
    )
    (net (code "65") (name "USART2_TX") (class "Default")
      (node (ref "TELEM1") (pin "2") (pinfunction "2_2") (pintype "passive"))
      (node (ref "U1") (pin "25") (pinfunction "PA2_25") (pintype "passive"))
    )
    (net (code "66") (name "VCAP1") (class "Default")
      (node (ref "C1") (pin "2") (pinfunction "2_2") (pintype "passive"))
      (node (ref "U1") (pin "49") (pinfunction "VCAP_1_49") (pintype "passive"))
    )
    (net (code "67") (name "VCAP2") (class "Default")
      (node (ref "C2") (pin "2") (pinfunction "2_2") (pintype "passive"))
      (node (ref "U1") (pin "73") (pinfunction "VCAP_2_73") (pintype "passive"))
    )
    (net (code "68") (name "VDDA") (class "Default")
      (node (ref "C11") (pin "1") (pinfunction "1_1") (pintype "passive"))
      (node (ref "C12") (pin "1") (pinfunction "1_1") (pintype "passive"))
      (node (ref "U1") (pin "22") (pinfunction "VDDA_22") (pintype "passive"))
    )
    (net (code "69") (name "VSSA") (class "Default")
      (node (ref "C13") (pin "1") (pinfunction "1_1") (pintype "passive"))
      (node (ref "R1") (pin "1") (pinfunction "1_1") (pintype "passive"))
      (node (ref "U1") (pin "20") (pinfunction "VSSA_20") (pintype "passive"))
    )
    (net (code "70") (name "unconnected-(TELEM2-Pad8)") (class "Default")
      (node (ref "TELEM2") (pin "8") (pinfunction "8_8") (pintype "passive"))
    )
    (net (code "71") (name "unconnected-(TELEM2-Pad9)") (class "Default")
      (node (ref "TELEM2") (pin "9") (pinfunction "9_9") (pintype "passive"))
    )
    (net (code "72") (name "unconnected-(TELEM2-Pad10)") (class "Default")
      (node (ref "TELEM2") (pin "10") (pinfunction "10_10") (pintype "passive"))
    )
    (net (code "73") (name "unconnected-(U1-PA4-Pad29)") (class "Default")
      (node (ref "U1") (pin "29") (pinfunction "PA4_29") (pintype "passive"))
    )
    (net (code "74") (name "unconnected-(U1-PA10-Pad69)") (class "Default")
      (node (ref "U1") (pin "69") (pinfunction "PA10_69") (pintype "passive"))
    )
    (net (code "75") (name "unconnected-(U1-PA15_(JTDI)-Pad77)") (class "Default")
      (node (ref "U1") (pin "77") (pinfunction "PA15_(JTDI)_77") (pintype "passive"))
    )
    (net (code "76") (name "unconnected-(U1-PB1-Pad36)") (class "Default")
      (node (ref "U1") (pin "36") (pinfunction "PB1_36") (pintype "passive"))
    )
    (net (code "77") (name "unconnected-(U1-PB2{slash}BOOT1_(PB2)-Pad37)") (class "Default")
      (node (ref "U1") (pin "37") (pinfunction "PB2/BOOT1_(PB2)_37") (pintype "passive"))
    )
    (net (code "78") (name "unconnected-(U1-PB4_(NJTRST)-Pad90)") (class "Default")
      (node (ref "U1") (pin "90") (pinfunction "PB4_(NJTRST)_90") (pintype "passive"))
    )
    (net (code "79") (name "unconnected-(U1-PB9-Pad96)") (class "Default")
      (node (ref "U1") (pin "96") (pinfunction "PB9_96") (pintype "passive"))
    )
    (net (code "80") (name "unconnected-(U1-PB12-Pad51)") (class "Default")
      (node (ref "U1") (pin "51") (pinfunction "PB12_51") (pintype "passive"))
    )
    (net (code "81") (name "unconnected-(U1-PB13-Pad52)") (class "Default")
      (node (ref "U1") (pin "52") (pinfunction "PB13_52") (pintype "passive"))
    )
    (net (code "82") (name "unconnected-(U1-PC0-Pad15)") (class "Default")
      (node (ref "U1") (pin "15") (pinfunction "PC0_15") (pintype "passive"))
    )
    (net (code "83") (name "unconnected-(U1-PC1-Pad16)") (class "Default")
      (node (ref "U1") (pin "16") (pinfunction "PC1_16") (pintype "passive"))
    )
    (net (code "84") (name "unconnected-(U1-PC2-Pad17)") (class "Default")
      (node (ref "U1") (pin "17") (pinfunction "PC2_17") (pintype "passive"))
    )
    (net (code "85") (name "unconnected-(U1-PC3-Pad18)") (class "Default")
      (node (ref "U1") (pin "18") (pinfunction "PC3_18") (pintype "passive"))
    )
    (net (code "86") (name "unconnected-(U1-PC6-Pad63)") (class "Default")
      (node (ref "U1") (pin "63") (pinfunction "PC6_63") (pintype "passive"))
    )
    (net (code "87") (name "unconnected-(U1-PC7-Pad64)") (class "Default")
      (node (ref "U1") (pin "64") (pinfunction "PC7_64") (pintype "passive"))
    )
    (net (code "88") (name "unconnected-(U1-PC8-Pad65)") (class "Default")
      (node (ref "U1") (pin "65") (pinfunction "PC8_65") (pintype "passive"))
    )
    (net (code "89") (name "unconnected-(U1-PC9-Pad66)") (class "Default")
      (node (ref "U1") (pin "66") (pinfunction "PC9_66") (pintype "passive"))
    )
    (net (code "90") (name "unconnected-(U1-PC10-Pad78)") (class "Default")
      (node (ref "U1") (pin "78") (pinfunction "PC10_78") (pintype "passive"))
    )
    (net (code "91") (name "unconnected-(U1-PC11-Pad79)") (class "Default")
      (node (ref "U1") (pin "79") (pinfunction "PC11_79") (pintype "passive"))
    )
    (net (code "92") (name "unconnected-(U1-PC13-Pad7)") (class "Default")
      (node (ref "U1") (pin "7") (pinfunction "PC13_7") (pintype "passive"))
    )
    (net (code "93") (name "unconnected-(U1-PD0-Pad81)") (class "Default")
      (node (ref "U1") (pin "81") (pinfunction "PD0_81") (pintype "passive"))
    )
    (net (code "94") (name "unconnected-(U1-PD1-Pad82)") (class "Default")
      (node (ref "U1") (pin "82") (pinfunction "PD1_82") (pintype "passive"))
    )
    (net (code "95") (name "unconnected-(U1-PD5-Pad86)") (class "Default")
      (node (ref "U1") (pin "86") (pinfunction "PD5_86") (pintype "passive"))
    )
    (net (code "96") (name "unconnected-(U1-PD6-Pad87)") (class "Default")
      (node (ref "U1") (pin "87") (pinfunction "PD6_87") (pintype "passive"))
    )
    (net (code "97") (name "unconnected-(U1-PD7-Pad88)") (class "Default")
      (node (ref "U1") (pin "88") (pinfunction "PD7_88") (pintype "passive"))
    )
    (net (code "98") (name "unconnected-(U1-PD8-Pad55)") (class "Default")
      (node (ref "U1") (pin "55") (pinfunction "PD8_55") (pintype "passive"))
    )
    (net (code "99") (name "unconnected-(U1-PD9-Pad56)") (class "Default")
      (node (ref "U1") (pin "56") (pinfunction "PD9_56") (pintype "passive"))
    )
    (net (code "100") (name "unconnected-(U1-PD10-Pad57)") (class "Default")
      (node (ref "U1") (pin "57") (pinfunction "PD10_57") (pintype "passive"))
    )
    (net (code "101") (name "unconnected-(U1-PD11-Pad58)") (class "Default")
      (node (ref "U1") (pin "58") (pinfunction "PD11_58") (pintype "passive"))
    )
    (net (code "102") (name "unconnected-(U1-PE0-Pad97)") (class "Default")
      (node (ref "U1") (pin "97") (pinfunction "PE0_97") (pintype "passive"))
    )
    (net (code "103") (name "unconnected-(U1-PE1-Pad98)") (class "Default")
      (node (ref "U1") (pin "98") (pinfunction "PE1_98") (pintype "passive"))
    )
    (net (code "104") (name "unconnected-(U1-PE2-Pad1)") (class "Default")
      (node (ref "U1") (pin "1") (pinfunction "PE2_1") (pintype "passive"))
    )
    (net (code "105") (name "unconnected-(U1-PE3-Pad2)") (class "Default")
      (node (ref "U1") (pin "2") (pinfunction "PE3_2") (pintype "passive"))
    )
    (net (code "106") (name "unconnected-(U1-PE4-Pad3)") (class "Default")
      (node (ref "U1") (pin "3") (pinfunction "PE4_3") (pintype "passive"))
    )
    (net (code "107") (name "unconnected-(U1-PE5-Pad4)") (class "Default")
      (node (ref "U1") (pin "4") (pinfunction "PE5_4") (pintype "passive"))
    )
    (net (code "108") (name "unconnected-(U1-PE6-Pad5)") (class "Default")
      (node (ref "U1") (pin "5") (pinfunction "PE6_5") (pintype "passive"))
    )
    (net (code "109") (name "unconnected-(U1-PE7-Pad38)") (class "Default")
      (node (ref "U1") (pin "38") (pinfunction "PE7_38") (pintype "passive"))
    )
    (net (code "110") (name "unconnected-(U1-PE8-Pad39)") (class "Default")
      (node (ref "U1") (pin "39") (pinfunction "PE8_39") (pintype "passive"))
    )
    (net (code "111") (name "unconnected-(U1-PE10-Pad41)") (class "Default")
      (node (ref "U1") (pin "41") (pinfunction "PE10_41") (pintype "passive"))
    )
    (net (code "112") (name "unconnected-(U1-PE12-Pad43)") (class "Default")
      (node (ref "U1") (pin "43") (pinfunction "PE12_43") (pintype "passive"))
    )
    (net (code "113") (name "unconnected-(U1-PE15-Pad46)") (class "Default")
      (node (ref "U1") (pin "46") (pinfunction "PE15_46") (pintype "passive"))
    )
    (net (code "114") (name "unconnected-(U4-AUX_CL-Pad7)") (class "Default")
      (node (ref "U4") (pin "7") (pinfunction "AUX_CL_7") (pintype "output"))
    )
    (net (code "115") (name "unconnected-(U4-AUX_DA-Pad6)") (class "Default")
      (node (ref "U4") (pin "6") (pinfunction "AUX_DA_6") (pintype "bidirectional"))
    )
    (net (code "116") (name "unconnected-(U4-CLKOUT-Pad22)") (class "Default")
      (node (ref "U4") (pin "22") (pinfunction "CLKOUT_22") (pintype "output"))
    )
    (net (code "117") (name "unconnected-(U4-EP-Pad25)") (class "Default")
      (node (ref "U4") (pin "25") (pinfunction "EP_25") (pintype "power_in"))
    )
    (net (code "118") (name "unconnected-(U4-NC-Pad2)") (class "Default")
      (node (ref "U4") (pin "2") (pinfunction "NC_2") (pintype "passive"))
    )
    (net (code "119") (name "unconnected-(U4-NC-Pad3)") (class "Default")
      (node (ref "U4") (pin "3") (pinfunction "NC_3") (pintype "passive"))
    )
    (net (code "120") (name "unconnected-(U4-NC-Pad4)") (class "Default")
      (node (ref "U4") (pin "4") (pinfunction "NC_4") (pintype "passive"))
    )
    (net (code "121") (name "unconnected-(U4-NC-Pad5)") (class "Default")
      (node (ref "U4") (pin "5") (pinfunction "NC_5") (pintype "passive"))
    )
    (net (code "122") (name "unconnected-(U4-NC-Pad14)") (class "Default")
      (node (ref "U4") (pin "14") (pinfunction "NC_14") (pintype "passive"))
    )
    (net (code "123") (name "unconnected-(U4-NC-Pad15)") (class "Default")
      (node (ref "U4") (pin "15") (pinfunction "NC_15") (pintype "passive"))
    )
    (net (code "124") (name "unconnected-(U4-NC-Pad16)") (class "Default")
      (node (ref "U4") (pin "16") (pinfunction "NC_16") (pintype "passive"))
    )
    (net (code "125") (name "unconnected-(U4-NC-Pad17)") (class "Default")
      (node (ref "U4") (pin "17") (pinfunction "NC_17") (pintype "passive"))
    )
    (net (code "126") (name "unconnected-(U4-RESV-Pad19)") (class "Default")
      (node (ref "U4") (pin "19") (pinfunction "RESV_19") (pintype "passive"))
    )
    (net (code "127") (name "unconnected-(U4-RESV-Pad21)") (class "Default")
      (node (ref "U4") (pin "21") (pinfunction "RESV_21") (pintype "passive"))
    )
    (net (code "128") (name "unconnected-(U4-VDD-Pad13)") (class "Default")
      (node (ref "U4") (pin "13") (pinfunction "VDD_13") (pintype "power_in"))
    )
    (net (code "129") (name "unconnected-(U5-VREF-Pad5)") (class "Default")
      (node (ref "U5") (pin "5") (pinfunction "VREF_5") (pintype "output"))
    )
    (net (code "130") (name "unconnected-(U6-VREF-Pad5)") (class "Default")
      (node (ref "U6") (pin "5") (pinfunction "VREF_5") (pintype "output"))
    )
  )
)
